# Memory.net
KiCad netlist of a schematic drawn in Altium Designer
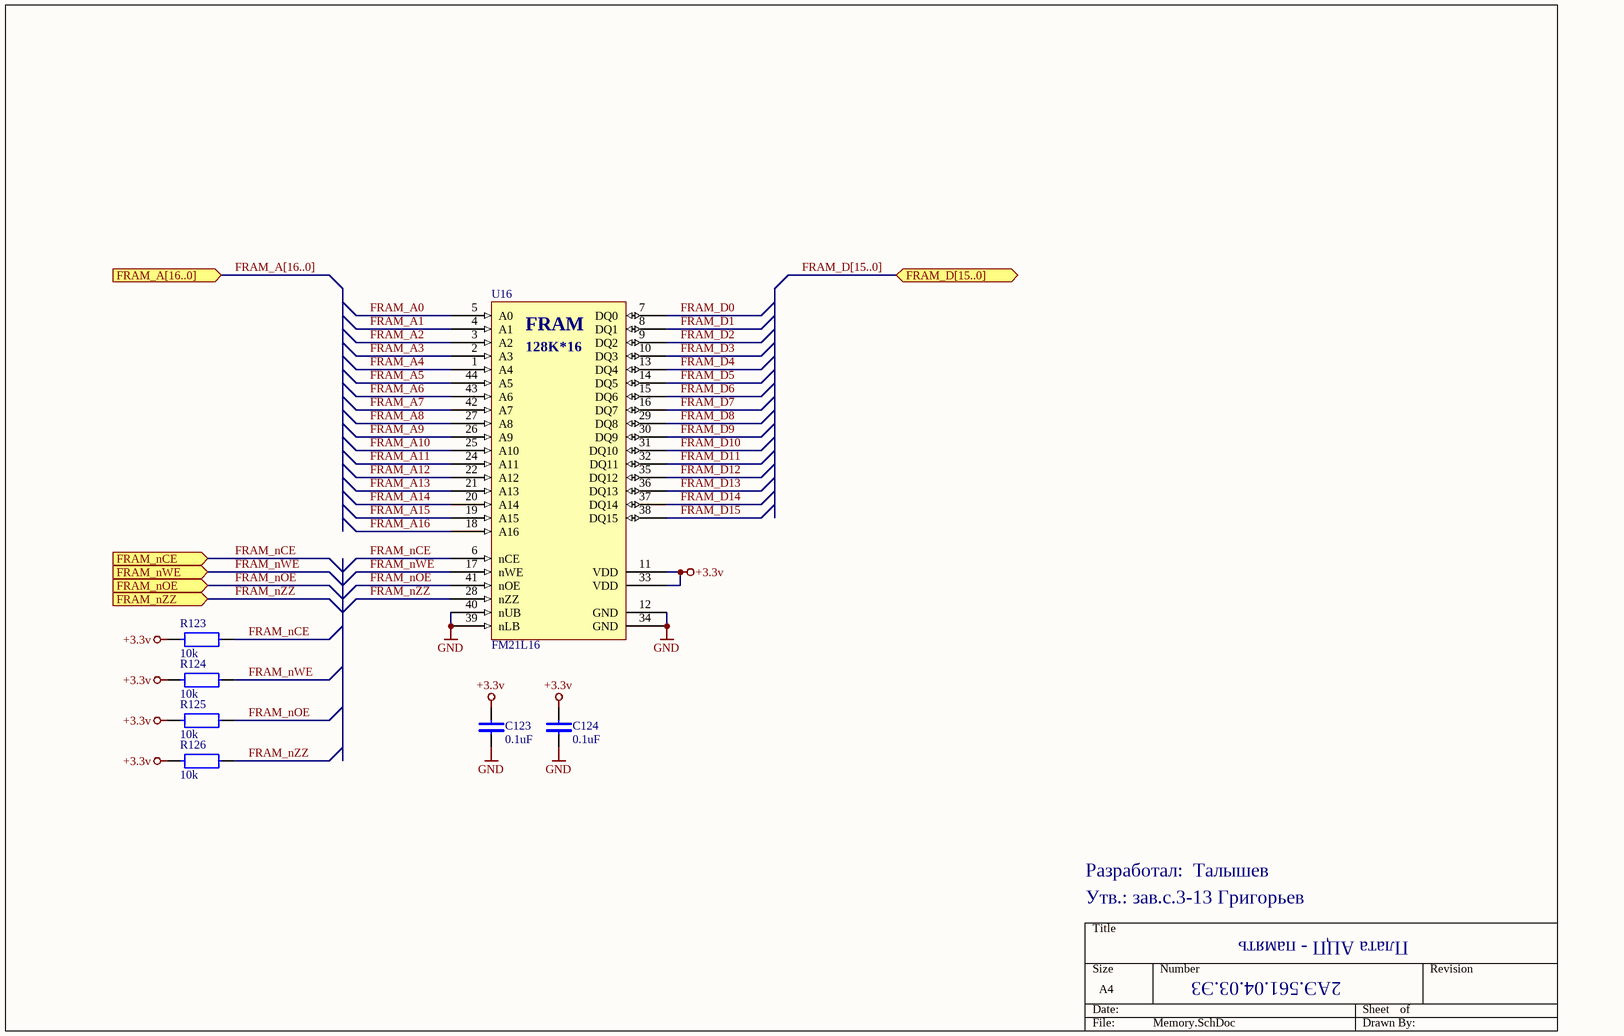
[diagram p0: Memory.SchDoc]

(export (version "E")
  (design (tool "Eeschema 10.0.6"))
  (components
    (comp (ref "C123") (value "0.1uF") (footprint "0603") (libsource (lib "*") (part "C")))
    (comp (ref "C124") (value "0.1uF") (footprint "0603") (libsource (lib "*") (part "C")))
    (comp (ref "R123") (value "10k") (footprint "0603") (libsource (lib "*") (part "R")))
    (comp (ref "R124") (value "10k") (footprint "0603") (libsource (lib "*") (part "R")))
    (comp (ref "R125") (value "10k") (footprint "0603") (libsource (lib "*") (part "R")))
    (comp (ref "R126") (value "10k") (footprint "0603") (libsource (lib "*") (part "R")))
    (comp (ref "U16")
      (value "FM21L16")
      (footprint "TSOP-II-44")
      (description "2Mbit (128K*16) F-RAM Memory")
      (libsource (lib "Mylib") (part "FM21L16"))
    )
  )
  (nets
    (net (code "1") (name "+3.3v") (class "Default")
      (node (ref "C123") (pin "2") (pinfunction "2_2") (pintype "passive"))
      (node (ref "C124") (pin "2") (pinfunction "2_2") (pintype "passive"))
      (node (ref "R123") (pin "2") (pinfunction "2_2") (pintype "passive"))
      (node (ref "R124") (pin "2") (pinfunction "2_2") (pintype "passive"))
      (node (ref "R125") (pin "2") (pinfunction "2_2") (pintype "passive"))
      (node (ref "R126") (pin "2") (pinfunction "2_2") (pintype "passive"))
      (node (ref "U16") (pin "11") (pinfunction "VDD_11") (pintype "passive"))
      (node (ref "U16") (pin "33") (pinfunction "VDD_33") (pintype "passive"))
    )
    (net (code "2") (name "/FRAM_A0") (class "Default")
      (node (ref "U16") (pin "5") (pinfunction "A0_5") (pintype "input"))
    )
    (net (code "3") (name "/FRAM_A1") (class "Default")
      (node (ref "U16") (pin "4") (pinfunction "A1_4") (pintype "input"))
    )
    (net (code "4") (name "/FRAM_A2") (class "Default")
      (node (ref "U16") (pin "3") (pinfunction "A2_3") (pintype "input"))
    )
    (net (code "5") (name "/FRAM_A3") (class "Default")
      (node (ref "U16") (pin "2") (pinfunction "A3_2") (pintype "input"))
    )
    (net (code "6") (name "/FRAM_A4") (class "Default")
      (node (ref "U16") (pin "1") (pinfunction "A4_1") (pintype "input"))
    )
    (net (code "7") (name "/FRAM_A5") (class "Default")
      (node (ref "U16") (pin "44") (pinfunction "A5_44") (pintype "input"))
    )
    (net (code "8") (name "/FRAM_A6") (class "Default")
      (node (ref "U16") (pin "43") (pinfunction "A6_43") (pintype "input"))
    )
    (net (code "9") (name "/FRAM_A7") (class "Default")
      (node (ref "U16") (pin "42") (pinfunction "A7_42") (pintype "input"))
    )
    (net (code "10") (name "/FRAM_A8") (class "Default")
      (node (ref "U16") (pin "27") (pinfunction "A8_27") (pintype "input"))
    )
    (net (code "11") (name "/FRAM_A9") (class "Default")
      (node (ref "U16") (pin "26") (pinfunction "A9_26") (pintype "input"))
    )
    (net (code "12") (name "/FRAM_A10") (class "Default")
      (node (ref "U16") (pin "25") (pinfunction "A10_25") (pintype "input"))
    )
    (net (code "13") (name "/FRAM_A11") (class "Default")
      (node (ref "U16") (pin "24") (pinfunction "A11_24") (pintype "input"))
    )
    (net (code "14") (name "/FRAM_A12") (class "Default")
      (node (ref "U16") (pin "22") (pinfunction "A12_22") (pintype "input"))
    )
    (net (code "15") (name "/FRAM_A13") (class "Default")
      (node (ref "U16") (pin "21") (pinfunction "A13_21") (pintype "input"))
    )
    (net (code "16") (name "/FRAM_A14") (class "Default")
      (node (ref "U16") (pin "20") (pinfunction "A14_20") (pintype "input"))
    )
    (net (code "17") (name "/FRAM_A15") (class "Default")
      (node (ref "U16") (pin "19") (pinfunction "A15_19") (pintype "input"))
    )
    (net (code "18") (name "/FRAM_A16") (class "Default")
      (node (ref "U16") (pin "18") (pinfunction "A16_18") (pintype "input"))
    )
    (net (code "20") (name "/FRAM_D0") (class "Default")
      (node (ref "U16") (pin "7") (pinfunction "DQ0_7") (pintype "bidirectional"))
    )
    (net (code "21") (name "/FRAM_D1") (class "Default")
      (node (ref "U16") (pin "8") (pinfunction "DQ1_8") (pintype "bidirectional"))
    )
    (net (code "22") (name "/FRAM_D2") (class "Default")
      (node (ref "U16") (pin "9") (pinfunction "DQ2_9") (pintype "bidirectional"))
    )
    (net (code "23") (name "/FRAM_D3") (class "Default")
      (node (ref "U16") (pin "10") (pinfunction "DQ3_10") (pintype "bidirectional"))
    )
    (net (code "24") (name "/FRAM_D4") (class "Default")
      (node (ref "U16") (pin "13") (pinfunction "DQ4_13") (pintype "bidirectional"))
    )
    (net (code "25") (name "/FRAM_D5") (class "Default")
      (node (ref "U16") (pin "14") (pinfunction "DQ5_14") (pintype "bidirectional"))
    )
    (net (code "26") (name "/FRAM_D6") (class "Default")
      (node (ref "U16") (pin "15") (pinfunction "DQ6_15") (pintype "bidirectional"))
    )
    (net (code "27") (name "/FRAM_D7") (class "Default")
      (node (ref "U16") (pin "16") (pinfunction "DQ7_16") (pintype "bidirectional"))
    )
    (net (code "28") (name "/FRAM_D8") (class "Default")
      (node (ref "U16") (pin "29") (pinfunction "DQ8_29") (pintype "bidirectional"))
    )
    (net (code "29") (name "/FRAM_D9") (class "Default")
      (node (ref "U16") (pin "30") (pinfunction "DQ9_30") (pintype "bidirectional"))
    )
    (net (code "30") (name "/FRAM_D10") (class "Default")
      (node (ref "U16") (pin "31") (pinfunction "DQ10_31") (pintype "bidirectional"))
    )
    (net (code "31") (name "/FRAM_D11") (class "Default")
      (node (ref "U16") (pin "32") (pinfunction "DQ11_32") (pintype "bidirectional"))
    )
    (net (code "32") (name "/FRAM_D12") (class "Default")
      (node (ref "U16") (pin "35") (pinfunction "DQ12_35") (pintype "bidirectional"))
    )
    (net (code "33") (name "/FRAM_D13") (class "Default")
      (node (ref "U16") (pin "36") (pinfunction "DQ13_36") (pintype "bidirectional"))
    )
    (net (code "34") (name "/FRAM_D14") (class "Default")
      (node (ref "U16") (pin "37") (pinfunction "DQ14_37") (pintype "bidirectional"))
    )
    (net (code "35") (name "/FRAM_D15") (class "Default")
      (node (ref "U16") (pin "38") (pinfunction "DQ15_38") (pintype "bidirectional"))
    )
    (net (code "37") (name "/FRAM_nCE") (class "Default")
      (node (ref "R123") (pin "1") (pinfunction "1_1") (pintype "passive"))
      (node (ref "U16") (pin "6") (pinfunction "nCE_6") (pintype "input"))
    )
    (net (code "38") (name "/FRAM_nOE") (class "Default")
      (node (ref "R125") (pin "1") (pinfunction "1_1") (pintype "passive"))
      (node (ref "U16") (pin "41") (pinfunction "nOE_41") (pintype "input"))
    )
    (net (code "39") (name "/FRAM_nWE") (class "Default")
      (node (ref "R124") (pin "1") (pinfunction "1_1") (pintype "passive"))
      (node (ref "U16") (pin "17") (pinfunction "nWE_17") (pintype "input"))
    )
    (net (code "40") (name "/FRAM_nZZ") (class "Default")
      (node (ref "R126") (pin "1") (pinfunction "1_1") (pintype "passive"))
      (node (ref "U16") (pin "28") (pinfunction "nZZ_28") (pintype "input"))
    )
    (net (code "41") (name "GND") (class "Default")
      (node (ref "C123") (pin "1") (pinfunction "1_1") (pintype "passive"))
      (node (ref "C124") (pin "1") (pinfunction "1_1") (pintype "passive"))
      (node (ref "U16") (pin "12") (pinfunction "GND_12") (pintype "passive"))
      (node (ref "U16") (pin "34") (pinfunction "GND_34") (pintype "passive"))
      (node (ref "U16") (pin "39") (pinfunction "nLB_39") (pintype "input"))
      (node (ref "U16") (pin "40") (pinfunction "nUB_40") (pintype "input"))
    )
  )
)
